# femtoBeacon_coin_nRF52832_BT4_2_r1_0_0.net
KiCad netlist of a schematic drawn in EAGLE
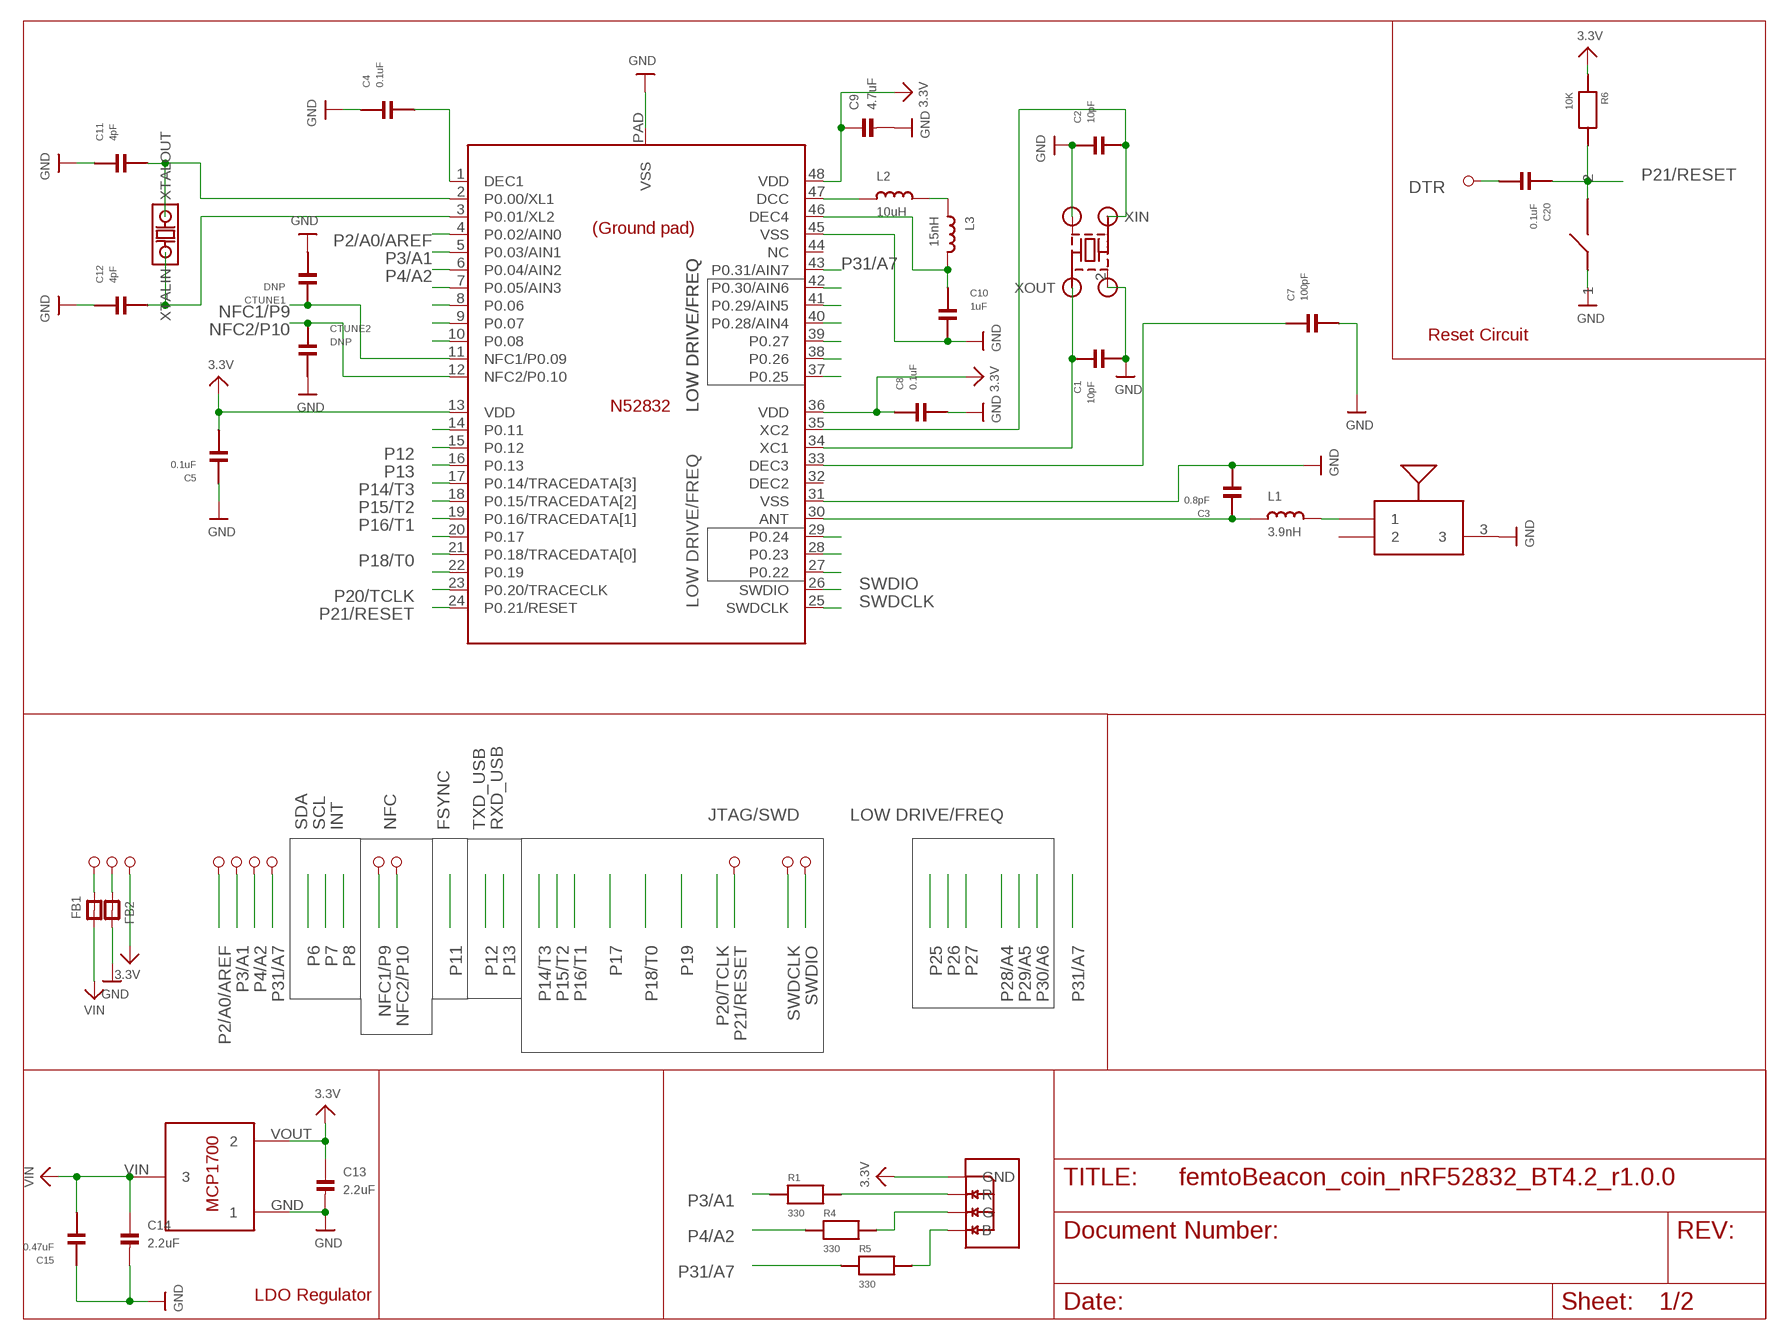
[diagram p0: schematic, sheet 1]
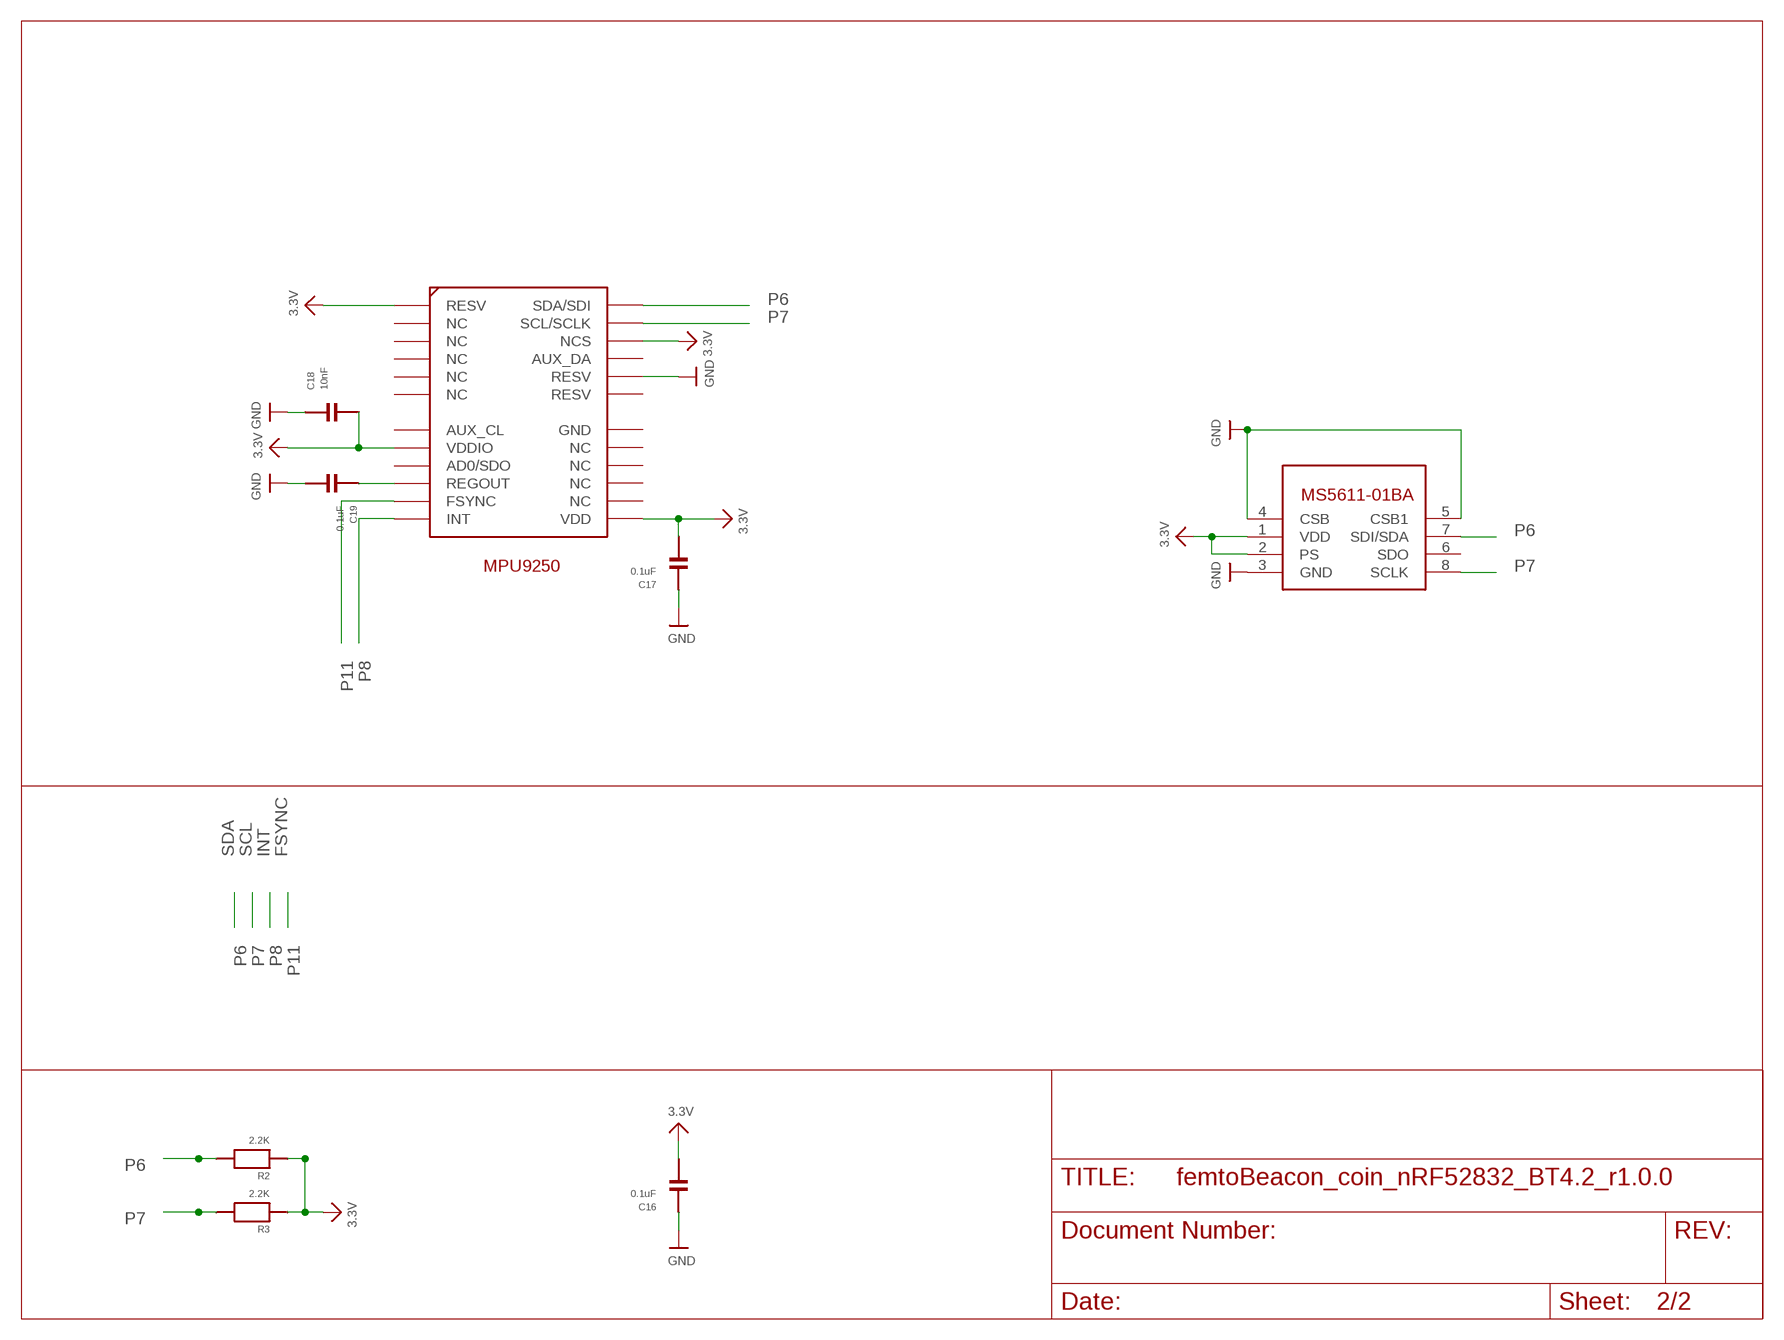
[diagram p1: schematic, sheet 2]

(export (version "E")
  (design (tool "Eeschema 10.0.6"))
  (components
    (comp (ref "BARO1")
      (value "MS5611-01BA03")
      (footprint "eagle-import:MS5611-01BA03")
      (libsource (lib "eagle-import") (part "MS5611-01BA03"))
    )
    (comp (ref "C16")
      (value "0.1uF")
      (footprint "eagle-import:PART")
      (libsource (lib "eagle-import") (part "CAPACITOR_0201"))
    )
    (comp (ref "C17")
      (value "0.1uF")
      (footprint "eagle-import:PART")
      (libsource (lib "eagle-import") (part "CAPACITOR_0201"))
    )
    (comp (ref "C18")
      (value "10nF")
      (footprint "eagle-import:PART")
      (libsource (lib "eagle-import") (part "CAPACITOR_0201"))
    )
    (comp (ref "C19")
      (value "0.1uF")
      (footprint "eagle-import:PART")
      (libsource (lib "eagle-import") (part "CAPACITOR_0201"))
    )
    (comp (ref "IMU1")
      (value "MPU-9250")
      (footprint "eagle-import:QFN_3X3MM")
      (libsource (lib "eagle-import") (part "MPU-9250"))
    )
    (comp (ref "R2")
      (value "2.2K")
      (footprint "eagle-import:PART")
      (libsource (lib "eagle-import") (part "RESISTOR_0201"))
    )
    (comp (ref "R3")
      (value "2.2K")
      (footprint "eagle-import:PART")
      (libsource (lib "eagle-import") (part "RESISTOR_0201"))
    )
    (comp (ref "ANTBAR")
      (value "PULSE_ANT_2.4GHZ")
      (footprint "eagle-import:ANT_BAR")
      (libsource (lib "eagle-import") (part "PULSE_ANT_2.4GHZ"))
    )
    (comp (ref "C1")
      (value "10pF")
      (footprint "eagle-import:PART")
      (libsource (lib "eagle-import") (part "CAPACITOR_0201"))
    )
    (comp (ref "C2")
      (value "10pF")
      (footprint "eagle-import:PART")
      (libsource (lib "eagle-import") (part "CAPACITOR_0201"))
    )
    (comp (ref "C3")
      (value "0.8pF")
      (footprint "eagle-import:PART")
      (libsource (lib "eagle-import") (part "CAPACITOR_0201"))
    )
    (comp (ref "C4")
      (value "0.1uF")
      (footprint "eagle-import:PART")
      (libsource (lib "eagle-import") (part "CAPACITOR_0201"))
    )
    (comp (ref "C5")
      (value "0.1uF")
      (footprint "eagle-import:PART")
      (libsource (lib "eagle-import") (part "CAPACITOR_0201"))
    )
    (comp (ref "C7")
      (value "100pF")
      (footprint "eagle-import:PART")
      (libsource (lib "eagle-import") (part "CAPACITOR_0201"))
    )
    (comp (ref "C8")
      (value "0.1uF")
      (footprint "eagle-import:PART")
      (libsource (lib "eagle-import") (part "CAPACITOR_0201"))
    )
    (comp (ref "C9")
      (value "4.7uF")
      (footprint "eagle-import:_0402MP")
      (libsource (lib "eagle-import") (part "CAP_CERAMIC_0402MP"))
    )
    (comp (ref "C10")
      (value "1uF")
      (footprint "eagle-import:PART")
      (libsource (lib "eagle-import") (part "CAPACITOR_0201"))
    )
    (comp (ref "C11")
      (value "4pF")
      (footprint "eagle-import:PART")
      (libsource (lib "eagle-import") (part "CAPACITOR_0201"))
    )
    (comp (ref "C12")
      (value "4pF")
      (footprint "eagle-import:PART")
      (libsource (lib "eagle-import") (part "CAPACITOR_0201"))
    )
    (comp (ref "C13")
      (value "2.2uF")
      (footprint "eagle-import:_0402MP")
      (libsource (lib "eagle-import") (part "CAP_CERAMIC_0402MP"))
    )
    (comp (ref "C14")
      (value "2.2uF")
      (footprint "eagle-import:_0402MP")
      (libsource (lib "eagle-import") (part "CAP_CERAMIC_0402MP"))
    )
    (comp (ref "C15")
      (value "0.47uF")
      (footprint "eagle-import:PART")
      (libsource (lib "eagle-import") (part "CAPACITOR_0201"))
    )
    (comp (ref "C20")
      (value "0.1uF")
      (footprint "eagle-import:PART")
      (libsource (lib "eagle-import") (part "CAPACITOR_0201"))
    )
    (comp (ref "CTUNE1")
      (value "DNP")
      (footprint "eagle-import:PART")
      (libsource (lib "eagle-import") (part "CAPACITOR_0201"))
    )
    (comp (ref "CTUNE2")
      (value "DNP")
      (footprint "eagle-import:PART")
      (libsource (lib "eagle-import") (part "CAPACITOR_0201"))
    )
    (comp (ref "FB1")
      (value "FERRITE_0603MP")
      (footprint "eagle-import:_0603MP")
      (libsource (lib "eagle-import") (part "FERRITE_0603MP"))
    )
    (comp (ref "FB2")
      (value "FERRITE_0603MP")
      (footprint "eagle-import:_0603MP")
      (libsource (lib "eagle-import") (part "FERRITE_0603MP"))
    )
    (comp (ref "IC1")
      (value "NRF52832_QFN48")
      (footprint "eagle-import:QFN48")
      (libsource (lib "eagle-import") (part "NRF52832_QFN48"))
    )
    (comp (ref "L1")
      (value "3.9nH")
      (footprint "eagle-import:_0402MP")
      (libsource (lib "eagle-import") (part "INDUCTOR_0402MP"))
    )
    (comp (ref "L2")
      (value "10uH")
      (footprint "eagle-import:_0603MP")
      (libsource (lib "eagle-import") (part "INDUCTOR_0603MP"))
    )
    (comp (ref "L3")
      (value "15nH")
      (footprint "eagle-import:_0402MP")
      (libsource (lib "eagle-import") (part "INDUCTOR_0402MP"))
    )
    (comp (ref "LDO_VREG")
      (value "MCP1700T-3302E/TT")
      (footprint "eagle-import:MCP1700T-3302E_TT")
      (libsource (lib "eagle-import") (part "MCP1700T-3302E/TT"))
    )
    (comp (ref "LED1")
      (value "LRTB_R48G")
      (footprint "eagle-import:LRTB_R48G")
      (libsource (lib "eagle-import") (part "LRTB_R48G"))
    )
    (comp (ref "PIN1")
      (value "1X1_ROUND")
      (footprint "eagle-import:1X1_ROUND")
      (libsource (lib "eagle-import") (part "1X1_ROUND"))
    )
    (comp (ref "PIN2")
      (value "1X1_ROUND")
      (footprint "eagle-import:1X1_ROUND")
      (libsource (lib "eagle-import") (part "1X1_ROUND"))
    )
    (comp (ref "PIN3")
      (value "1X1_ROUND")
      (footprint "eagle-import:1X1_ROUND")
      (libsource (lib "eagle-import") (part "1X1_ROUND"))
    )
    (comp (ref "PIN4")
      (value "1X1_ROUND")
      (footprint "eagle-import:1X1_ROUND")
      (libsource (lib "eagle-import") (part "1X1_ROUND"))
    )
    (comp (ref "PIN7")
      (value "1X1_ROUND")
      (footprint "eagle-import:1X1_ROUND")
      (libsource (lib "eagle-import") (part "1X1_ROUND"))
    )
    (comp (ref "PIN8")
      (value "1X1_ROUND")
      (footprint "eagle-import:1X1_ROUND")
      (libsource (lib "eagle-import") (part "1X1_ROUND"))
    )
    (comp (ref "PIN9")
      (value "1X1_ROUND")
      (footprint "eagle-import:1X1_ROUND")
      (libsource (lib "eagle-import") (part "1X1_ROUND"))
    )
    (comp (ref "PIN10")
      (value "1X1_ROUND")
      (footprint "eagle-import:1X1_ROUND")
      (libsource (lib "eagle-import") (part "1X1_ROUND"))
    )
    (comp (ref "PIN13")
      (value "1X1_ROUND")
      (footprint "eagle-import:1X1_ROUND")
      (libsource (lib "eagle-import") (part "1X1_ROUND"))
    )
    (comp (ref "PIN14")
      (value "1X1_ROUND")
      (footprint "eagle-import:1X1_ROUND")
      (libsource (lib "eagle-import") (part "1X1_ROUND"))
    )
    (comp (ref "PIN25")
      (value "1X1_ROUND")
      (footprint "eagle-import:1X1_ROUND")
      (libsource (lib "eagle-import") (part "1X1_ROUND"))
    )
    (comp (ref "PIN26")
      (value "1X1_ROUND")
      (footprint "eagle-import:1X1_ROUND")
      (libsource (lib "eagle-import") (part "1X1_ROUND"))
    )
    (comp (ref "PIN27")
      (value "1X1_ROUND")
      (footprint "eagle-import:1X1_ROUND")
      (libsource (lib "eagle-import") (part "1X1_ROUND"))
    )
    (comp (ref "R1")
      (value "330")
      (footprint "eagle-import:PART")
      (libsource (lib "eagle-import") (part "RESISTOR_0201"))
    )
    (comp (ref "R4")
      (value "330")
      (footprint "eagle-import:PART")
      (libsource (lib "eagle-import") (part "RESISTOR_0201"))
    )
    (comp (ref "R5")
      (value "330")
      (footprint "eagle-import:PART")
      (libsource (lib "eagle-import") (part "RESISTOR_0201"))
    )
    (comp (ref "R6")
      (value "10K")
      (footprint "eagle-import:PART")
      (libsource (lib "eagle-import") (part "RESISTOR_0201"))
    )
    (comp (ref "RESET_JMP")
      (value "SPST_SMD")
      (footprint "eagle-import:SPST_SMD")
      (libsource (lib "eagle-import") (part "SPST_SMD"))
    )
    (comp (ref "XOSC32K")
      (value "ABS06-107-32.768KHZ-T")
      (footprint "eagle-import:ABS06-107-32.768KHZ-T")
      (libsource (lib "eagle-import") (part "ABS06-107-32.768KHZ-T"))
    )
    (comp (ref "XTAL")
      (value "32MHz")
      (footprint "eagle-import:ABM11")
      (libsource (lib "eagle-import") (part "ABM11-48.000MHZ-D2X-T3"))
    )
  )
  (nets
    (net (code "1") (name "3.3V") (class "Default")
      (node (ref "BARO1") (pin "1") (pinfunction "VDD_1") (pintype "bidirectional"))
      (node (ref "BARO1") (pin "2") (pinfunction "PS_2") (pintype "bidirectional"))
      (node (ref "C13") (pin "1") (pinfunction "P$1_1") (pintype "passive"))
      (node (ref "C16") (pin "2") (pinfunction "P$2_2") (pintype "bidirectional"))
      (node (ref "C17") (pin "2") (pinfunction "P$2_2") (pintype "bidirectional"))
      (node (ref "C18") (pin "2") (pinfunction "P$2_2") (pintype "bidirectional"))
      (node (ref "C5") (pin "2") (pinfunction "P$2_2") (pintype "bidirectional"))
      (node (ref "C8") (pin "1") (pinfunction "P$1_1") (pintype "bidirectional"))
      (node (ref "C9") (pin "1") (pinfunction "P$1_1") (pintype "passive"))
      (node (ref "IC1") (pin "13") (pinfunction "VDD_13") (pintype "bidirectional"))
      (node (ref "IC1") (pin "36") (pinfunction "VDD_36") (pintype "bidirectional"))
      (node (ref "IC1") (pin "48") (pinfunction "VDD_48") (pintype "bidirectional"))
      (node (ref "IMU1") (pin "P$1") (pinfunction "RESV_P$1") (pintype "bidirectional"))
      (node (ref "IMU1") (pin "P$13") (pinfunction "VDD_P$13") (pintype "bidirectional"))
      (node (ref "IMU1") (pin "P$22") (pinfunction "NCS_P$22") (pintype "bidirectional"))
      (node (ref "IMU1") (pin "P$8") (pinfunction "VDDIO_P$8") (pintype "bidirectional"))
      (node (ref "LDO_VREG") (pin "VOUT") (pinfunction "2_VOUT") (pintype "bidirectional"))
      (node (ref "LED1") (pin "1") (pinfunction "GND_1") (pintype "bidirectional"))
      (node (ref "PIN3") (pin "P$1") (pinfunction "1_P$1") (pintype "bidirectional"))
      (node (ref "R2") (pin "1") (pinfunction "1_1") (pintype "bidirectional"))
      (node (ref "R3") (pin "1") (pinfunction "1_1") (pintype "bidirectional"))
      (node (ref "R6") (pin "1") (pinfunction "1_1") (pintype "bidirectional"))
    )
    (net (code "2") (name "DTR") (class "Default")
      (node (ref "C20") (pin "2") (pinfunction "P$2_2") (pintype "bidirectional"))
      (node (ref "PIN4") (pin "P$1") (pinfunction "1_P$1") (pintype "bidirectional"))
    )
    (net (code "3") (name "GND") (class "Default")
      (node (ref "ANTBAR") (pin "3") (pinfunction "3_3") (pintype "bidirectional"))
      (node (ref "BARO1") (pin "3") (pinfunction "GND_3") (pintype "bidirectional"))
      (node (ref "BARO1") (pin "4") (pinfunction "CSB_4") (pintype "bidirectional"))
      (node (ref "BARO1") (pin "5") (pinfunction "CSB1_5") (pintype "bidirectional"))
      (node (ref "C1") (pin "2") (pinfunction "P$2_2") (pintype "bidirectional"))
      (node (ref "C10") (pin "2") (pinfunction "P$2_2") (pintype "bidirectional"))
      (node (ref "C11") (pin "1") (pinfunction "P$1_1") (pintype "bidirectional"))
      (node (ref "C12") (pin "1") (pinfunction "P$1_1") (pintype "bidirectional"))
      (node (ref "C13") (pin "2") (pinfunction "P$2_2") (pintype "passive"))
      (node (ref "C14") (pin "2") (pinfunction "P$2_2") (pintype "passive"))
      (node (ref "C15") (pin "1") (pinfunction "P$1_1") (pintype "bidirectional"))
      (node (ref "C16") (pin "1") (pinfunction "P$1_1") (pintype "bidirectional"))
      (node (ref "C17") (pin "1") (pinfunction "P$1_1") (pintype "bidirectional"))
      (node (ref "C18") (pin "1") (pinfunction "P$1_1") (pintype "bidirectional"))
      (node (ref "C19") (pin "2") (pinfunction "P$2_2") (pintype "bidirectional"))
      (node (ref "C2") (pin "1") (pinfunction "P$1_1") (pintype "bidirectional"))
      (node (ref "C3") (pin "2") (pinfunction "P$2_2") (pintype "bidirectional"))
      (node (ref "C4") (pin "1") (pinfunction "P$1_1") (pintype "bidirectional"))
      (node (ref "C5") (pin "1") (pinfunction "P$1_1") (pintype "bidirectional"))
      (node (ref "C7") (pin "2") (pinfunction "P$2_2") (pintype "bidirectional"))
      (node (ref "C8") (pin "2") (pinfunction "P$2_2") (pintype "bidirectional"))
      (node (ref "C9") (pin "2") (pinfunction "P$2_2") (pintype "passive"))
      (node (ref "CTUNE1") (pin "2") (pinfunction "P$2_2") (pintype "bidirectional"))
      (node (ref "CTUNE2") (pin "2") (pinfunction "P$2_2") (pintype "bidirectional"))
      (node (ref "FB2") (pin "2") (pinfunction "P$2_2") (pintype "passive"))
      (node (ref "IC1") (pin "31") (pinfunction "VSS_31") (pintype "bidirectional"))
      (node (ref "IC1") (pin "45") (pinfunction "VSS_45") (pintype "bidirectional"))
      (node (ref "IC1") (pin "PAD") (pinfunction "VSS_PAD") (pintype "bidirectional"))
      (node (ref "IMU1") (pin "P$20") (pinfunction "RESV_P$20") (pintype "bidirectional"))
      (node (ref "LDO_VREG") (pin "GND") (pinfunction "1_GND") (pintype "bidirectional"))
      (node (ref "RESET_JMP") (pin "1") (pinfunction "1_1") (pintype "bidirectional"))
      (node (ref "XTAL") (pin "2") (pinfunction "GND_2") (pintype "bidirectional"))
      (node (ref "XTAL") (pin "4") (pinfunction "GND_4") (pintype "bidirectional"))
    )
    (net (code "4") (name "NFC1{slash}P9") (class "Default")
      (node (ref "CTUNE1") (pin "1") (pinfunction "P$1_1") (pintype "bidirectional"))
      (node (ref "IC1") (pin "11") (pinfunction "NFC1/P0.09_11") (pintype "bidirectional"))
      (node (ref "PIN13") (pin "P$1") (pinfunction "1_P$1") (pintype "bidirectional"))
    )
    (net (code "5") (name "NFC2{slash}P10") (class "Default")
      (node (ref "CTUNE2") (pin "1") (pinfunction "P$1_1") (pintype "bidirectional"))
      (node (ref "IC1") (pin "12") (pinfunction "NFC2/P0.10_12") (pintype "bidirectional"))
      (node (ref "PIN14") (pin "P$1") (pinfunction "1_P$1") (pintype "bidirectional"))
    )
    (net (code "6") (name "Net-(ANTBAR-Pad1)") (class "Default")
      (node (ref "ANTBAR") (pin "1") (pinfunction "1_1") (pintype "bidirectional"))
      (node (ref "L1") (pin "2") (pinfunction "2_2") (pintype "passive"))
    )
    (net (code "7") (name "Net-(C1-P$1)") (class "Default")
      (node (ref "C1") (pin "1") (pinfunction "P$1_1") (pintype "bidirectional"))
      (node (ref "IC1") (pin "34") (pinfunction "XC1_34") (pintype "bidirectional"))
      (node (ref "XTAL") (pin "3") (pinfunction "XOUT_3") (pintype "bidirectional"))
    )
    (net (code "8") (name "Net-(C2-P$2)") (class "Default")
      (node (ref "C2") (pin "2") (pinfunction "P$2_2") (pintype "bidirectional"))
      (node (ref "IC1") (pin "35") (pinfunction "XC2_35") (pintype "bidirectional"))
      (node (ref "XTAL") (pin "1") (pinfunction "XIN_1") (pintype "bidirectional"))
    )
    (net (code "9") (name "Net-(C3-P$1)") (class "Default")
      (node (ref "C3") (pin "1") (pinfunction "P$1_1") (pintype "bidirectional"))
      (node (ref "IC1") (pin "30") (pinfunction "ANT_30") (pintype "bidirectional"))
      (node (ref "L1") (pin "1") (pinfunction "1_1") (pintype "passive"))
    )
    (net (code "10") (name "Net-(C4-P$2)") (class "Default")
      (node (ref "C4") (pin "2") (pinfunction "P$2_2") (pintype "bidirectional"))
      (node (ref "IC1") (pin "1") (pinfunction "DEC1_1") (pintype "bidirectional"))
    )
    (net (code "11") (name "Net-(C7-P$1)") (class "Default")
      (node (ref "C7") (pin "1") (pinfunction "P$1_1") (pintype "bidirectional"))
      (node (ref "IC1") (pin "33") (pinfunction "DEC3_33") (pintype "bidirectional"))
    )
    (net (code "12") (name "Net-(C10-P$1)") (class "Default")
      (node (ref "C10") (pin "1") (pinfunction "P$1_1") (pintype "bidirectional"))
      (node (ref "IC1") (pin "46") (pinfunction "DEC4_46") (pintype "bidirectional"))
      (node (ref "L3") (pin "2") (pinfunction "2_2") (pintype "passive"))
    )
    (net (code "13") (name "Net-(C11-P$2)") (class "Default")
      (node (ref "C11") (pin "2") (pinfunction "P$2_2") (pintype "bidirectional"))
      (node (ref "IC1") (pin "2") (pinfunction "P0.00/XL1_2") (pintype "bidirectional"))
      (node (ref "XOSC32K") (pin "2") (pinfunction "XTALOUT_2") (pintype "bidirectional"))
    )
    (net (code "14") (name "Net-(C12-P$2)") (class "Default")
      (node (ref "C12") (pin "2") (pinfunction "P$2_2") (pintype "bidirectional"))
      (node (ref "IC1") (pin "3") (pinfunction "P0.01/XL2_3") (pintype "bidirectional"))
      (node (ref "XOSC32K") (pin "1") (pinfunction "XTALIN_1") (pintype "bidirectional"))
    )
    (net (code "15") (name "Net-(C19-P$1)") (class "Default")
      (node (ref "C19") (pin "1") (pinfunction "P$1_1") (pintype "bidirectional"))
      (node (ref "IMU1") (pin "P$10") (pinfunction "REGOUT_P$10") (pintype "bidirectional"))
    )
    (net (code "16") (name "Net-(FB1-P$2)") (class "Default")
      (node (ref "FB1") (pin "2") (pinfunction "P$2_2") (pintype "passive"))
      (node (ref "PIN1") (pin "P$1") (pinfunction "1_P$1") (pintype "bidirectional"))
    )
    (net (code "17") (name "Net-(FB2-P$1)") (class "Default")
      (node (ref "FB2") (pin "1") (pinfunction "P$1_1") (pintype "passive"))
      (node (ref "PIN2") (pin "P$1") (pinfunction "1_P$1") (pintype "bidirectional"))
    )
    (net (code "18") (name "Net-(IC1-DCC)") (class "Default")
      (node (ref "IC1") (pin "47") (pinfunction "DCC_47") (pintype "bidirectional"))
      (node (ref "L2") (pin "1") (pinfunction "1_1") (pintype "passive"))
    )
    (net (code "19") (name "Net-(L2-Pad2)") (class "Default")
      (node (ref "L2") (pin "2") (pinfunction "2_2") (pintype "passive"))
      (node (ref "L3") (pin "1") (pinfunction "1_1") (pintype "passive"))
    )
    (net (code "20") (name "Net-(LED1-B)") (class "Default")
      (node (ref "LED1") (pin "4") (pinfunction "B_4") (pintype "bidirectional"))
      (node (ref "R5") (pin "2") (pinfunction "2_2") (pintype "bidirectional"))
    )
    (net (code "21") (name "Net-(LED1-G)") (class "Default")
      (node (ref "LED1") (pin "3") (pinfunction "G_3") (pintype "bidirectional"))
      (node (ref "R4") (pin "2") (pinfunction "2_2") (pintype "bidirectional"))
    )
    (net (code "22") (name "Net-(LED1-R)") (class "Default")
      (node (ref "LED1") (pin "2") (pinfunction "R_2") (pintype "bidirectional"))
      (node (ref "R1") (pin "2") (pinfunction "2_2") (pintype "bidirectional"))
    )
    (net (code "23") (name "P2{slash}A0{slash}AREF") (class "Default")
      (node (ref "IC1") (pin "4") (pinfunction "P0.02/AIN0_4") (pintype "bidirectional"))
      (node (ref "PIN9") (pin "P$1") (pinfunction "1_P$1") (pintype "bidirectional"))
    )
    (net (code "24") (name "P3{slash}A1") (class "Default")
      (node (ref "IC1") (pin "5") (pinfunction "P0.03/AIN1_5") (pintype "bidirectional"))
      (node (ref "PIN10") (pin "P$1") (pinfunction "1_P$1") (pintype "bidirectional"))
      (node (ref "R1") (pin "1") (pinfunction "1_1") (pintype "bidirectional"))
    )
    (net (code "25") (name "P4{slash}A2") (class "Default")
      (node (ref "IC1") (pin "6") (pinfunction "P0.04/AIN2_6") (pintype "bidirectional"))
      (node (ref "PIN7") (pin "P$1") (pinfunction "1_P$1") (pintype "bidirectional"))
      (node (ref "R4") (pin "1") (pinfunction "1_1") (pintype "bidirectional"))
    )
    (net (code "26") (name "P6") (class "Default")
      (node (ref "BARO1") (pin "7") (pinfunction "SDI/SDA_7") (pintype "bidirectional"))
      (node (ref "IC1") (pin "8") (pinfunction "P0.06_8") (pintype "bidirectional"))
      (node (ref "IMU1") (pin "P$24") (pinfunction "SDA/SDI_P$24") (pintype "bidirectional"))
      (node (ref "R2") (pin "2") (pinfunction "2_2") (pintype "bidirectional"))
    )
    (net (code "27") (name "P7") (class "Default")
      (node (ref "BARO1") (pin "8") (pinfunction "SCLK_8") (pintype "bidirectional"))
      (node (ref "IC1") (pin "9") (pinfunction "P0.07_9") (pintype "bidirectional"))
      (node (ref "IMU1") (pin "P$23") (pinfunction "SCL/SCLK_P$23") (pintype "bidirectional"))
      (node (ref "R3") (pin "2") (pinfunction "2_2") (pintype "bidirectional"))
    )
    (net (code "28") (name "P8") (class "Default")
      (node (ref "IC1") (pin "10") (pinfunction "P0.08_10") (pintype "bidirectional"))
      (node (ref "IMU1") (pin "P$12") (pinfunction "INT_P$12") (pintype "bidirectional"))
    )
    (net (code "29") (name "P11") (class "Default")
      (node (ref "IC1") (pin "14") (pinfunction "P0.11_14") (pintype "bidirectional"))
      (node (ref "IMU1") (pin "P$11") (pinfunction "FSYNC_P$11") (pintype "bidirectional"))
    )
    (net (code "30") (name "P12") (class "Default")
      (node (ref "IC1") (pin "15") (pinfunction "P0.12_15") (pintype "bidirectional"))
    )
    (net (code "31") (name "P13") (class "Default")
      (node (ref "IC1") (pin "16") (pinfunction "P0.13_16") (pintype "bidirectional"))
    )
    (net (code "32") (name "P14{slash}T3") (class "Default")
      (node (ref "IC1") (pin "17") (pinfunction "P0.14/TRACEDATA[3]_17") (pintype "bidirectional"))
    )
    (net (code "33") (name "P15{slash}T2") (class "Default")
      (node (ref "IC1") (pin "18") (pinfunction "P0.15/TRACEDATA[2]_18") (pintype "bidirectional"))
    )
    (net (code "34") (name "P16{slash}T1") (class "Default")
      (node (ref "IC1") (pin "19") (pinfunction "P0.16/TRACEDATA[1]_19") (pintype "bidirectional"))
    )
    (net (code "35") (name "P17") (class "Default")
      (node (ref "IC1") (pin "20") (pinfunction "P0.17_20") (pintype "bidirectional"))
    )
    (net (code "36") (name "P18{slash}T0") (class "Default")
      (node (ref "IC1") (pin "21") (pinfunction "P0.18/TRACEDATA[0]_21") (pintype "bidirectional"))
    )
    (net (code "37") (name "P19") (class "Default")
      (node (ref "IC1") (pin "22") (pinfunction "P0.19_22") (pintype "bidirectional"))
    )
    (net (code "38") (name "P20{slash}TCLK") (class "Default")
      (node (ref "IC1") (pin "23") (pinfunction "P0.20/TRACECLK_23") (pintype "bidirectional"))
    )
    (net (code "39") (name "P21{slash}RESET") (class "Default")
      (node (ref "C20") (pin "1") (pinfunction "P$1_1") (pintype "bidirectional"))
      (node (ref "IC1") (pin "24") (pinfunction "P0.21/RESET_24") (pintype "bidirectional"))
      (node (ref "PIN25") (pin "P$1") (pinfunction "1_P$1") (pintype "bidirectional"))
      (node (ref "R6") (pin "2") (pinfunction "2_2") (pintype "bidirectional"))
      (node (ref "RESET_JMP") (pin "2") (pinfunction "2_2") (pintype "bidirectional"))
    )
    (net (code "40") (name "P25") (class "Default")
      (node (ref "IC1") (pin "37") (pinfunction "P0.25_37") (pintype "bidirectional"))
    )
    (net (code "41") (name "P26") (class "Default")
      (node (ref "IC1") (pin "38") (pinfunction "P0.26_38") (pintype "bidirectional"))
    )
    (net (code "42") (name "P27") (class "Default")
      (node (ref "IC1") (pin "39") (pinfunction "P0.27_39") (pintype "bidirectional"))
    )
    (net (code "43") (name "P28{slash}A4") (class "Default")
      (node (ref "IC1") (pin "40") (pinfunction "P0.28/AIN4_40") (pintype "bidirectional"))
    )
    (net (code "44") (name "P29{slash}A5") (class "Default")
      (node (ref "IC1") (pin "41") (pinfunction "P0.29/AIN5_41") (pintype "bidirectional"))
    )
    (net (code "45") (name "P30{slash}A6") (class "Default")
      (node (ref "IC1") (pin "42") (pinfunction "P0.30/AIN6_42") (pintype "bidirectional"))
    )
    (net (code "46") (name "P31{slash}A7") (class "Default")
      (node (ref "IC1") (pin "43") (pinfunction "P0.31/AIN7_43") (pintype "bidirectional"))
      (node (ref "PIN8") (pin "P$1") (pinfunction "1_P$1") (pintype "bidirectional"))
      (node (ref "R5") (pin "1") (pinfunction "1_1") (pintype "bidirectional"))
    )
    (net (code "47") (name "SWDCLK") (class "Default")
      (node (ref "IC1") (pin "25") (pinfunction "SWDCLK_25") (pintype "bidirectional"))
      (node (ref "PIN26") (pin "P$1") (pinfunction "1_P$1") (pintype "bidirectional"))
    )
    (net (code "48") (name "SWDIO") (class "Default")
      (node (ref "IC1") (pin "26") (pinfunction "SWDIO_26") (pintype "bidirectional"))
      (node (ref "PIN27") (pin "P$1") (pinfunction "1_P$1") (pintype "bidirectional"))
    )
    (net (code "49") (name "VIN") (class "Default")
      (node (ref "C14") (pin "1") (pinfunction "P$1_1") (pintype "passive"))
      (node (ref "C15") (pin "2") (pinfunction "P$2_2") (pintype "bidirectional"))
      (node (ref "FB1") (pin "1") (pinfunction "P$1_1") (pintype "passive"))
      (node (ref "LDO_VREG") (pin "VIN") (pinfunction "3_VIN") (pintype "bidirectional"))
    )
    (net (code "50") (name "unconnected-(ANTBAR-Pad2)") (class "Default")
      (node (ref "ANTBAR") (pin "2") (pinfunction "2_2") (pintype "bidirectional"))
    )
    (net (code "51") (name "unconnected-(BARO1-SDO-Pad6)") (class "Default")
      (node (ref "BARO1") (pin "6") (pinfunction "SDO_6") (pintype "bidirectional"))
    )
    (net (code "52") (name "unconnected-(IC1-DEC2-Pad32)") (class "Default")
      (node (ref "IC1") (pin "32") (pinfunction "DEC2_32") (pintype "bidirectional"))
    )
    (net (code "53") (name "unconnected-(IC1-NC-Pad44)") (class "Default")
      (node (ref "IC1") (pin "44") (pinfunction "NC_44") (pintype "bidirectional"))
    )
    (net (code "54") (name "unconnected-(IC1-P0.05{slash}AIN3-Pad7)") (class "Default")
      (node (ref "IC1") (pin "7") (pinfunction "P0.05/AIN3_7") (pintype "bidirectional"))
    )
    (net (code "55") (name "unconnected-(IC1-P0.22-Pad27)") (class "Default")
      (node (ref "IC1") (pin "27") (pinfunction "P0.22_27") (pintype "bidirectional"))
    )
    (net (code "56") (name "unconnected-(IC1-P0.23-Pad28)") (class "Default")
      (node (ref "IC1") (pin "28") (pinfunction "P0.23_28") (pintype "bidirectional"))
    )
    (net (code "57") (name "unconnected-(IC1-P0.24-Pad29)") (class "Default")
      (node (ref "IC1") (pin "29") (pinfunction "P0.24_29") (pintype "bidirectional"))
    )
    (net (code "58") (name "unconnected-(IMU1-AD0{slash}SDO-PadP$9)") (class "Default")
      (node (ref "IMU1") (pin "P$9") (pinfunction "AD0/SDO_P$9") (pintype "bidirectional"))
    )
    (net (code "59") (name "unconnected-(IMU1-AUX_CL-PadP$7)") (class "Default")
      (node (ref "IMU1") (pin "P$7") (pinfunction "AUX_CL_P$7") (pintype "bidirectional"))
    )
    (net (code "60") (name "unconnected-(IMU1-AUX_DA-PadP$21)") (class "Default")
      (node (ref "IMU1") (pin "P$21") (pinfunction "AUX_DA_P$21") (pintype "bidirectional"))
    )
    (net (code "61") (name "unconnected-(IMU1-GND-PadP$18)") (class "Default")
      (node (ref "IMU1") (pin "P$18") (pinfunction "GND_P$18") (pintype "bidirectional"))
    )
    (net (code "62") (name "unconnected-(IMU1-NC-PadP$2)") (class "Default")
      (node (ref "IMU1") (pin "P$2") (pinfunction "NC_P$2") (pintype "bidirectional"))
    )
    (net (code "63") (name "unconnected-(IMU1-NC-PadP$3)") (class "Default")
      (node (ref "IMU1") (pin "P$3") (pinfunction "NC_P$3") (pintype "bidirectional"))
    )
    (net (code "64") (name "unconnected-(IMU1-NC-PadP$4)") (class "Default")
      (node (ref "IMU1") (pin "P$4") (pinfunction "NC_P$4") (pintype "bidirectional"))
    )
    (net (code "65") (name "unconnected-(IMU1-NC-PadP$5)") (class "Default")
      (node (ref "IMU1") (pin "P$5") (pinfunction "NC_P$5") (pintype "bidirectional"))
    )
    (net (code "66") (name "unconnected-(IMU1-NC-PadP$6)") (class "Default")
      (node (ref "IMU1") (pin "P$6") (pinfunction "NC_P$6") (pintype "bidirectional"))
    )
    (net (code "67") (name "unconnected-(IMU1-NC-PadP$14)") (class "Default")
      (node (ref "IMU1") (pin "P$14") (pinfunction "NC_P$14") (pintype "bidirectional"))
    )
    (net (code "68") (name "unconnected-(IMU1-NC-PadP$15)") (class "Default")
      (node (ref "IMU1") (pin "P$15") (pinfunction "NC_P$15") (pintype "bidirectional"))
    )
    (net (code "69") (name "unconnected-(IMU1-NC-PadP$16)") (class "Default")
      (node (ref "IMU1") (pin "P$16") (pinfunction "NC_P$16") (pintype "bidirectional"))
    )
    (net (code "70") (name "unconnected-(IMU1-NC-PadP$17)") (class "Default")
      (node (ref "IMU1") (pin "P$17") (pinfunction "NC_P$17") (pintype "bidirectional"))
    )
    (net (code "71") (name "unconnected-(IMU1-RESV-PadP$19)") (class "Default")
      (node (ref "IMU1") (pin "P$19") (pinfunction "RESV_P$19") (pintype "bidirectional"))
    )
  )
)
